# relay.net
KiCad netlist of a schematic drawn in EAGLE
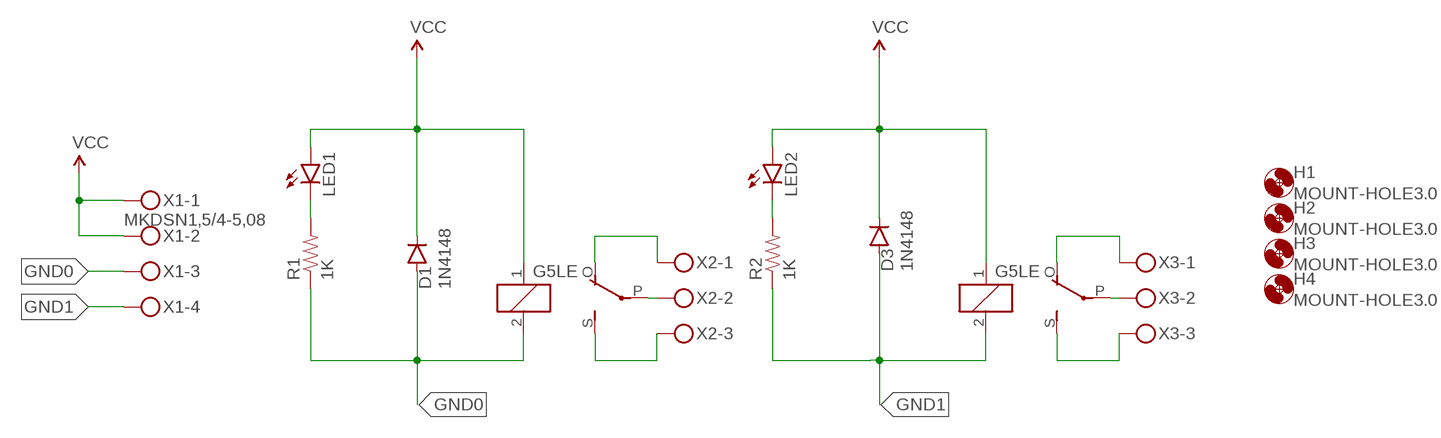
[diagram p0: schematic, sheet 1]

(export (version "E")
  (design (tool "Eeschema 10.0.6"))
  (components
    (comp (ref "D1")
      (value "1N4148")
      (footprint "eagle-import:DIODE-1N4148-KIT")
      (libsource (lib "eagle-import") (part "DIODEKIT"))
    )
    (comp (ref "D3")
      (value "1N4148")
      (footprint "eagle-import:DIODE-1N4148-KIT")
      (libsource (lib "eagle-import") (part "DIODEKIT"))
    )
    (comp (ref "H1")
      (value "MOUNT-HOLE3.0")
      (footprint "eagle-import:3,0")
      (libsource (lib "eagle-import") (part "MOUNT-HOLE3.0"))
    )
    (comp (ref "H2")
      (value "MOUNT-HOLE3.0")
      (footprint "eagle-import:3,0")
      (libsource (lib "eagle-import") (part "MOUNT-HOLE3.0"))
    )
    (comp (ref "H3")
      (value "MOUNT-HOLE3.0")
      (footprint "eagle-import:3,0")
      (libsource (lib "eagle-import") (part "MOUNT-HOLE3.0"))
    )
    (comp (ref "H4")
      (value "MOUNT-HOLE3.0")
      (footprint "eagle-import:3,0")
      (libsource (lib "eagle-import") (part "MOUNT-HOLE3.0"))
    )
    (comp (ref "K1")
      (value "G5LE")
      (footprint "eagle-import:G5LE")
      (libsource (lib "eagle-import") (part "G5LE"))
    )
    (comp (ref "K2")
      (value "G5LE")
      (footprint "eagle-import:G5LE")
      (libsource (lib "eagle-import") (part "G5LE"))
    )
    (comp (ref "LED1")
      (value "LED3MM")
      (footprint "eagle-import:LED3MM")
      (fields (field (name "PROD_ID") "DIO-09529"))
      (libsource (lib "eagle-import") (part "LED3MM"))
    )
    (comp (ref "LED2")
      (value "LED3MM")
      (footprint "eagle-import:LED3MM")
      (fields (field (name "PROD_ID") "DIO-09529"))
      (libsource (lib "eagle-import") (part "LED3MM"))
    )
    (comp (ref "R1")
      (value "1K")
      (footprint "eagle-import:AXIAL-0.3EZ")
      (libsource (lib "eagle-import") (part "1KOHM-1/4W-1%(PTH)HORIZ-KIT"))
    )
    (comp (ref "R2")
      (value "1K")
      (footprint "eagle-import:AXIAL-0.3EZ")
      (libsource (lib "eagle-import") (part "1KOHM-1/4W-1%(PTH)HORIZ-KIT"))
    )
    (comp (ref "X1")
      (value "MKDSN1,5/4-5,08")
      (footprint "eagle-import:MKDSN1,5_4-5,08")
      (libsource (lib "eagle-import") (part "MKDSN1,5/4-5,08"))
    )
    (comp (ref "X2")
      (value "MKDSN1,5/3-5,08")
      (footprint "eagle-import:MKDSN1,5_3-5,08")
      (libsource (lib "eagle-import") (part "MKDSN1,5/3-5,08"))
    )
    (comp (ref "X3")
      (value "MKDSN1,5/3-5,08")
      (footprint "eagle-import:MKDSN1,5_3-5,08")
      (libsource (lib "eagle-import") (part "MKDSN1,5/3-5,08"))
    )
  )
  (nets
    (net (code "1") (name "GND0") (class "Default")
      (node (ref "D1") (pin "A") (pinfunction "A_A") (pintype "passive"))
      (node (ref "K2") (pin "2") (pinfunction "2_2") (pintype "passive"))
      (node (ref "R1") (pin "P$1") (pinfunction "1_P$1") (pintype "passive"))
      (node (ref "X1") (pin "3") (pinfunction "KL_3") (pintype "passive"))
    )
    (net (code "2") (name "GND1") (class "Default")
      (node (ref "D3") (pin "A") (pinfunction "A_A") (pintype "passive"))
      (node (ref "K1") (pin "2") (pinfunction "2_2") (pintype "passive"))
      (node (ref "R2") (pin "P$1") (pinfunction "1_P$1") (pintype "passive"))
      (node (ref "X1") (pin "4") (pinfunction "KL_4") (pintype "passive"))
    )
    (net (code "3") (name "Net-(LED1-C)") (class "Default")
      (node (ref "LED1") (pin "K") (pinfunction "C_K") (pintype "passive"))
      (node (ref "R1") (pin "P$2") (pinfunction "2_P$2") (pintype "passive"))
    )
    (net (code "4") (name "Net-(LED2-C)") (class "Default")
      (node (ref "LED2") (pin "K") (pinfunction "C_K") (pintype "passive"))
      (node (ref "R2") (pin "P$2") (pinfunction "2_P$2") (pintype "passive"))
    )
    (net (code "5") (name "Net-(X2A-KL)") (class "Default")
      (node (ref "K2") (pin "O") (pinfunction "O_O") (pintype "passive"))
      (node (ref "X2") (pin "1") (pinfunction "KL_1") (pintype "passive"))
    )
    (net (code "6") (name "Net-(X2B-KL)") (class "Default")
      (node (ref "K2") (pin "P") (pinfunction "P_P") (pintype "passive"))
      (node (ref "X2") (pin "2") (pinfunction "KL_2") (pintype "passive"))
    )
    (net (code "7") (name "Net-(X2C-KL)") (class "Default")
      (node (ref "K2") (pin "S") (pinfunction "S_S") (pintype "passive"))
      (node (ref "X2") (pin "3") (pinfunction "KL_3") (pintype "passive"))
    )
    (net (code "8") (name "Net-(X3A-KL)") (class "Default")
      (node (ref "K1") (pin "O") (pinfunction "O_O") (pintype "passive"))
      (node (ref "X3") (pin "1") (pinfunction "KL_1") (pintype "passive"))
    )
    (net (code "9") (name "Net-(X3B-KL)") (class "Default")
      (node (ref "K1") (pin "P") (pinfunction "P_P") (pintype "passive"))
      (node (ref "X3") (pin "2") (pinfunction "KL_2") (pintype "passive"))
    )
    (net (code "10") (name "Net-(X3C-KL)") (class "Default")
      (node (ref "K1") (pin "S") (pinfunction "S_S") (pintype "passive"))
      (node (ref "X3") (pin "3") (pinfunction "KL_3") (pintype "passive"))
    )
    (net (code "11") (name "VCC") (class "Default")
      (node (ref "D1") (pin "C") (pinfunction "C_C") (pintype "passive"))
      (node (ref "D3") (pin "C") (pinfunction "C_C") (pintype "passive"))
      (node (ref "K1") (pin "1") (pinfunction "1_1") (pintype "passive"))
      (node (ref "K2") (pin "1") (pinfunction "1_1") (pintype "passive"))
      (node (ref "LED1") (pin "A") (pinfunction "A_A") (pintype "passive"))
      (node (ref "LED2") (pin "A") (pinfunction "A_A") (pintype "passive"))
      (node (ref "X1") (pin "1") (pinfunction "KL_1") (pintype "passive"))
      (node (ref "X1") (pin "2") (pinfunction "KL_2") (pintype "passive"))
    )
  )
)
